# seeed2040_dev_board_11-13-22.net
KiCad netlist of a schematic drawn in EAGLE
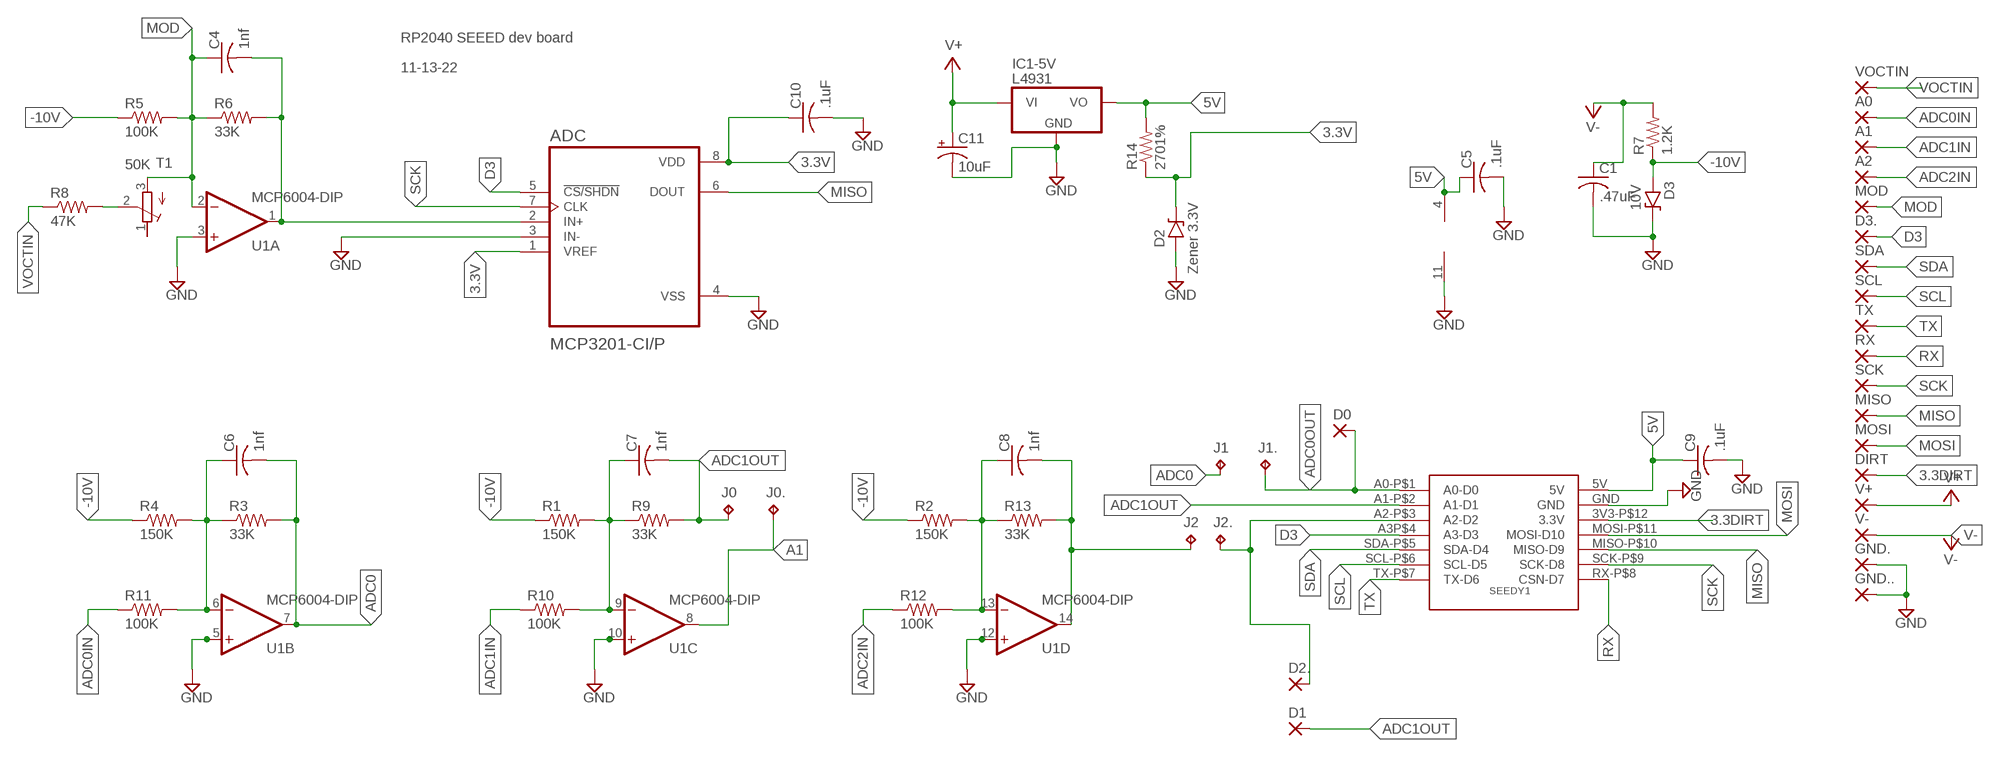
[diagram p0: schematic, sheet 1]

(export (version "E")
  (design (tool "Eeschema 10.0.6"))
  (components
    (comp (ref "A0")
      (value "WIREPAD1,6/0,9")
      (footprint "eagle-import:1,6_0,9")
      (libsource (lib "eagle-import") (part "WIREPAD1,6/0,9"))
    )
    (comp (ref "A1")
      (value "WIREPAD1,6/0,9")
      (footprint "eagle-import:1,6_0,9")
      (libsource (lib "eagle-import") (part "WIREPAD1,6/0,9"))
    )
    (comp (ref "A2")
      (value "WIREPAD1,6/0,9")
      (footprint "eagle-import:1,6_0,9")
      (libsource (lib "eagle-import") (part "WIREPAD1,6/0,9"))
    )
    (comp (ref "ADC")
      (value "MCP3201-CI/P")
      (footprint "eagle-import:DIP787W46P254L927H533Q8")
      (fields (field (name "MF") "Microchip Technology"))
      (libsource (lib "eagle-import") (part "MCP3201-CI/P"))
    )
    (comp (ref "C1")
      (value ".47uF")
      (footprint "eagle-import:C025-030X050")
      (libsource (lib "eagle-import") (part "rcl_334_C-US025-030X050"))
    )
    (comp (ref "C4")
      (value "1nf")
      (footprint "eagle-import:C025-025X050")
      (libsource (lib "eagle-import") (part "rcl_334_C-US025-025X050"))
    )
    (comp (ref "C5")
      (value ".1uF")
      (footprint "eagle-import:C025-025X050")
      (libsource (lib "eagle-import") (part "rcl_334_C-US025-025X050"))
    )
    (comp (ref "C6")
      (value "1nf")
      (footprint "eagle-import:C025-025X050")
      (libsource (lib "eagle-import") (part "rcl_334_C-US025-025X050"))
    )
    (comp (ref "C7")
      (value "1nf")
      (footprint "eagle-import:C025-025X050")
      (libsource (lib "eagle-import") (part "rcl_334_C-US025-025X050"))
    )
    (comp (ref "C8")
      (value "1nf")
      (footprint "eagle-import:C025-025X050")
      (libsource (lib "eagle-import") (part "rcl_334_C-US025-025X050"))
    )
    (comp (ref "C9")
      (value ".1uF")
      (footprint "eagle-import:C050-025X075")
      (libsource (lib "eagle-import") (part "C-US050-025X075"))
    )
    (comp (ref "C10")
      (value ".1uF")
      (footprint "eagle-import:C025-025X050")
      (libsource (lib "eagle-import") (part "rcl_334_C-US025-025X050"))
    )
    (comp (ref "C11")
      (value "10uF")
      (footprint "eagle-import:E2,5-7")
      (libsource (lib "eagle-import") (part "CPOL-USE2.5-7"))
    )
    (comp (ref "D0")
      (value "WIREPAD1,6/0,9")
      (footprint "eagle-import:1,6_0,9")
      (libsource (lib "eagle-import") (part "WIREPAD1,6/0,9"))
    )
    (comp (ref "D1")
      (value "WIREPAD1,6/0,9")
      (footprint "eagle-import:1,6_0,9")
      (libsource (lib "eagle-import") (part "WIREPAD1,6/0,9"))
    )
    (comp (ref "D2")
      (value "Zener 3.3V")
      (footprint "eagle-import:DO41-3")
      (libsource (lib "eagle-import") (part "ZENER.3"))
    )
    (comp (ref "D2.")
      (value "WIREPAD1,6/0,9")
      (footprint "eagle-import:1,6_0,9")
      (libsource (lib "eagle-import") (part "WIREPAD1,6/0,9"))
    )
    (comp (ref "D3")
      (value "10V")
      (footprint "eagle-import:DO41-3")
      (libsource (lib "eagle-import") (part "ZENER.3"))
    )
    (comp (ref "D3.")
      (value "WIREPAD1,6/0,9")
      (footprint "eagle-import:1,6_0,9")
      (libsource (lib "eagle-import") (part "WIREPAD1,6/0,9"))
    )
    (comp (ref "DIRT")
      (value "WIREPAD1,6/0,9")
      (footprint "eagle-import:1,6_0,9")
      (libsource (lib "eagle-import") (part "WIREPAD1,6/0,9"))
    )
    (comp (ref "GND.")
      (value "WIREPAD1,6/0,9")
      (footprint "eagle-import:1,6_0,9")
      (libsource (lib "eagle-import") (part "WIREPAD1,6/0,9"))
    )
    (comp (ref "GND..")
      (value "WIREPAD1,6/0,9")
      (footprint "eagle-import:1,6_0,9")
      (libsource (lib "eagle-import") (part "WIREPAD1,6/0,9"))
    )
    (comp (ref "IC1-5V")
      (value "L4931")
      (footprint "eagle-import:TO92-")
      (libsource (lib "eagle-import") (part "L4931"))
    )
    (comp (ref "J0")
      (value "TPPAD1-13")
      (footprint "eagle-import:P1-13")
      (libsource (lib "eagle-import") (part "TPPAD1-13"))
    )
    (comp (ref "J0.")
      (value "TPPAD1-13")
      (footprint "eagle-import:P1-13")
      (libsource (lib "eagle-import") (part "TPPAD1-13"))
    )
    (comp (ref "J1")
      (value "TPPAD1-13")
      (footprint "eagle-import:P1-13")
      (libsource (lib "eagle-import") (part "TPPAD1-13"))
    )
    (comp (ref "J1.")
      (value "TPPAD1-13")
      (footprint "eagle-import:P1-13")
      (libsource (lib "eagle-import") (part "TPPAD1-13"))
    )
    (comp (ref "J2")
      (value "TPPAD1-13")
      (footprint "eagle-import:P1-13")
      (libsource (lib "eagle-import") (part "TPPAD1-13"))
    )
    (comp (ref "J2.")
      (value "TPPAD1-13")
      (footprint "eagle-import:P1-13")
      (libsource (lib "eagle-import") (part "TPPAD1-13"))
    )
    (comp (ref "MISO")
      (value "WIREPAD1,6/0,9")
      (footprint "eagle-import:1,6_0,9")
      (libsource (lib "eagle-import") (part "WIREPAD1,6/0,9"))
    )
    (comp (ref "MOD")
      (value "WIREPAD1,6/0,9")
      (footprint "eagle-import:1,6_0,9")
      (libsource (lib "eagle-import") (part "WIREPAD1,6/0,9"))
    )
    (comp (ref "MOSI")
      (value "WIREPAD1,6/0,9")
      (footprint "eagle-import:1,6_0,9")
      (libsource (lib "eagle-import") (part "WIREPAD1,6/0,9"))
    )
    (comp (ref "R1")
      (value "150K")
      (footprint "eagle-import:0204_7")
      (libsource (lib "eagle-import") (part "R-US_0204/7"))
    )
    (comp (ref "R2")
      (value "150K")
      (footprint "eagle-import:0204_7")
      (libsource (lib "eagle-import") (part "R-US_0204/7"))
    )
    (comp (ref "R3")
      (value "33K")
      (footprint "eagle-import:0204_7")
      (libsource (lib "eagle-import") (part "R-US_0204/7"))
    )
    (comp (ref "R4")
      (value "150K")
      (footprint "eagle-import:0204_7")
      (libsource (lib "eagle-import") (part "R-US_0204/7"))
    )
    (comp (ref "R5")
      (value "100K")
      (footprint "eagle-import:0204_7")
      (libsource (lib "eagle-import") (part "R-US_0204/7"))
    )
    (comp (ref "R6")
      (value "33K")
      (footprint "eagle-import:0204_7")
      (libsource (lib "eagle-import") (part "R-US_0204/7"))
    )
    (comp (ref "R7")
      (value "1.2K")
      (footprint "eagle-import:0204_7")
      (libsource (lib "eagle-import") (part "R-US_0204/7"))
    )
    (comp (ref "R8")
      (value "47K")
      (footprint "eagle-import:0204_7")
      (libsource (lib "eagle-import") (part "R-US_0204/7"))
    )
    (comp (ref "R9")
      (value "33K")
      (footprint "eagle-import:0204_7")
      (libsource (lib "eagle-import") (part "R-US_0204/7"))
    )
    (comp (ref "R10")
      (value "100K")
      (footprint "eagle-import:0204_7")
      (libsource (lib "eagle-import") (part "R-US_0204/7"))
    )
    (comp (ref "R11")
      (value "100K")
      (footprint "eagle-import:0204_7")
      (libsource (lib "eagle-import") (part "R-US_0204/7"))
    )
    (comp (ref "R12")
      (value "100K")
      (footprint "eagle-import:0204_7")
      (libsource (lib "eagle-import") (part "R-US_0204/7"))
    )
    (comp (ref "R13")
      (value "33K")
      (footprint "eagle-import:0204_7")
      (libsource (lib "eagle-import") (part "R-US_0204/7"))
    )
    (comp (ref "R14")
      (value "2701%")
      (footprint "eagle-import:0204_7")
      (libsource (lib "eagle-import") (part "R-US_0204/7"))
    )
    (comp (ref "RX")
      (value "WIREPAD1,6/0,9")
      (footprint "eagle-import:1,6_0,9")
      (libsource (lib "eagle-import") (part "WIREPAD1,6/0,9"))
    )
    (comp (ref "SCK")
      (value "WIREPAD1,6/0,9")
      (footprint "eagle-import:1,6_0,9")
      (libsource (lib "eagle-import") (part "WIREPAD1,6/0,9"))
    )
    (comp (ref "SCL")
      (value "WIREPAD1,6/0,9")
      (footprint "eagle-import:1,6_0,9")
      (libsource (lib "eagle-import") (part "WIREPAD1,6/0,9"))
    )
    (comp (ref "SDA")
      (value "WIREPAD1,6/0,9")
      (footprint "eagle-import:1,6_0,9")
      (libsource (lib "eagle-import") (part "WIREPAD1,6/0,9"))
    )
    (comp (ref "SEEDY1")
      (value "SEEED_XIAO_RP2040")
      (footprint "eagle-import:14PIN700MIL")
      (libsource (lib "eagle-import") (part "SEEED_XIAO_RP2040"))
    )
    (comp (ref "T1")
      (value "50K")
      (footprint "eagle-import:RTRIMT93YA")
      (libsource (lib "eagle-import") (part "R-TRIMMT93YA"))
    )
    (comp (ref "TX")
      (value "WIREPAD1,6/0,9")
      (footprint "eagle-import:1,6_0,9")
      (libsource (lib "eagle-import") (part "WIREPAD1,6/0,9"))
    )
    (comp (ref "U1")
      (value "MCP6004-DIP")
      (footprint "eagle-import:DIL14")
      (libsource (lib "eagle-import") (part "MCP6004-DIP"))
    )
    (comp (ref "V+")
      (value "WIREPAD1,6/0,9")
      (footprint "eagle-import:1,6_0,9")
      (libsource (lib "eagle-import") (part "WIREPAD1,6/0,9"))
    )
    (comp (ref "V-")
      (value "WIREPAD1,6/0,9")
      (footprint "eagle-import:1,6_0,9")
      (libsource (lib "eagle-import") (part "WIREPAD1,6/0,9"))
    )
    (comp (ref "VOCTIN")
      (value "WIREPAD1,6/0,9")
      (footprint "eagle-import:1,6_0,9")
      (libsource (lib "eagle-import") (part "WIREPAD1,6/0,9"))
    )
  )
  (nets
    (net (code "1") (name "-10V") (class "Default")
      (node (ref "D3") (pin "A") (pinfunction "A_A") (pintype "passive"))
      (node (ref "R1") (pin "1") (pinfunction "1_1") (pintype "passive"))
      (node (ref "R2") (pin "1") (pinfunction "1_1") (pintype "passive"))
      (node (ref "R4") (pin "1") (pinfunction "1_1") (pintype "passive"))
      (node (ref "R5") (pin "1") (pinfunction "1_1") (pintype "passive"))
      (node (ref "R7") (pin "1") (pinfunction "1_1") (pintype "passive"))
    )
    (net (code "2") (name "3.3DIRT") (class "Default")
      (node (ref "DIRT") (pin "1") (pinfunction "P_1") (pintype "passive"))
      (node (ref "SEEDY1") (pin "3V3-P$12") (pinfunction "3.3V_3V3-P$12") (pintype "output"))
    )
    (net (code "3") (name "3.3V") (class "Default")
      (node (ref "ADC") (pin "1") (pinfunction "VREF_1") (pintype "input"))
      (node (ref "ADC") (pin "8") (pinfunction "VDD_8") (pintype "power_in"))
      (node (ref "C10") (pin "1") (pinfunction "1_1") (pintype "passive"))
      (node (ref "D2") (pin "C") (pinfunction "C_C") (pintype "passive"))
      (node (ref "R14") (pin "1") (pinfunction "1_1") (pintype "passive"))
    )
    (net (code "4") (name "5V") (class "Default")
      (node (ref "C5") (pin "1") (pinfunction "1_1") (pintype "passive"))
      (node (ref "C9") (pin "1") (pinfunction "1_1") (pintype "passive"))
      (node (ref "IC1-5V") (pin "3") (pinfunction "VO_3") (pintype "passive"))
      (node (ref "R14") (pin "2") (pinfunction "2_2") (pintype "passive"))
      (node (ref "SEEDY1") (pin "5V") (pinfunction "5V_5V") (pintype "power_in"))
      (node (ref "U1") (pin "4") (pinfunction "V+_4") (pintype "power_in"))
    )
    (net (code "5") (name "A1") (class "Default")
      (node (ref "J0.") (pin "TP") (pinfunction "TP_TP") (pintype "input"))
      (node (ref "U1") (pin "8") (pinfunction "OUT_8") (pintype "output"))
    )
    (net (code "6") (name "ADC0") (class "Default")
      (node (ref "C6") (pin "2") (pinfunction "2_2") (pintype "passive"))
      (node (ref "J1") (pin "TP") (pinfunction "TP_TP") (pintype "input"))
      (node (ref "R3") (pin "2") (pinfunction "2_2") (pintype "passive"))
      (node (ref "U1") (pin "7") (pinfunction "OUT_7") (pintype "output"))
    )
    (net (code "7") (name "ADC0IN") (class "Default")
      (node (ref "A0") (pin "1") (pinfunction "P_1") (pintype "passive"))
      (node (ref "R11") (pin "1") (pinfunction "1_1") (pintype "passive"))
    )
    (net (code "8") (name "ADC0OUT") (class "Default")
      (node (ref "D0") (pin "1") (pinfunction "P_1") (pintype "passive"))
      (node (ref "J1.") (pin "TP") (pinfunction "TP_TP") (pintype "input"))
      (node (ref "SEEDY1") (pin "A0-P$1") (pinfunction "A0-D0_A0-P$1") (pintype "bidirectional"))
    )
    (net (code "9") (name "ADC1IN") (class "Default")
      (node (ref "A1") (pin "1") (pinfunction "P_1") (pintype "passive"))
      (node (ref "R10") (pin "1") (pinfunction "1_1") (pintype "passive"))
    )
    (net (code "10") (name "ADC1OUT") (class "Default")
      (node (ref "C7") (pin "2") (pinfunction "2_2") (pintype "passive"))
      (node (ref "D1") (pin "1") (pinfunction "P_1") (pintype "passive"))
      (node (ref "J0") (pin "TP") (pinfunction "TP_TP") (pintype "input"))
      (node (ref "R9") (pin "2") (pinfunction "2_2") (pintype "passive"))
      (node (ref "SEEDY1") (pin "A1-P$2") (pinfunction "A1-D1_A1-P$2") (pintype "bidirectional"))
    )
    (net (code "11") (name "ADC2IN") (class "Default")
      (node (ref "A2") (pin "1") (pinfunction "P_1") (pintype "passive"))
      (node (ref "R12") (pin "1") (pinfunction "1_1") (pintype "passive"))
    )
    (net (code "12") (name "D3") (class "Default")
      (node (ref "ADC") (pin "5") (pinfunction "~{CS/SHDN}_5") (pintype "input"))
      (node (ref "D3.") (pin "1") (pinfunction "P_1") (pintype "passive"))
      (node (ref "SEEDY1") (pin "A3P$4") (pinfunction "A3-D3_A3P$4") (pintype "bidirectional"))
    )
    (net (code "13") (name "GND") (class "Default")
      (node (ref "ADC") (pin "3") (pinfunction "IN-_3") (pintype "input"))
      (node (ref "ADC") (pin "4") (pinfunction "VSS_4") (pintype "power_in"))
      (node (ref "C1") (pin "2") (pinfunction "2_2") (pintype "passive"))
      (node (ref "C10") (pin "2") (pinfunction "2_2") (pintype "passive"))
      (node (ref "C11") (pin "-") (pinfunction "-_-") (pintype "passive"))
      (node (ref "C5") (pin "2") (pinfunction "2_2") (pintype "passive"))
      (node (ref "C9") (pin "2") (pinfunction "2_2") (pintype "passive"))
      (node (ref "D2") (pin "A") (pinfunction "A_A") (pintype "passive"))
      (node (ref "D3") (pin "C") (pinfunction "C_C") (pintype "passive"))
      (node (ref "GND.") (pin "1") (pinfunction "P_1") (pintype "passive"))
      (node (ref "GND..") (pin "1") (pinfunction "P_1") (pintype "passive"))
      (node (ref "IC1-5V") (pin "2") (pinfunction "GND_2") (pintype "passive"))
      (node (ref "SEEDY1") (pin "GND") (pinfunction "GND_GND") (pintype "bidirectional"))
      (node (ref "U1") (pin "10") (pinfunction "+IN_10") (pintype "input"))
      (node (ref "U1") (pin "11") (pinfunction "V-_11") (pintype "power_in"))
      (node (ref "U1") (pin "12") (pinfunction "+IN_12") (pintype "input"))
      (node (ref "U1") (pin "3") (pinfunction "+IN_3") (pintype "input"))
      (node (ref "U1") (pin "5") (pinfunction "+IN_5") (pintype "input"))
    )
    (net (code "14") (name "MISO") (class "Default")
      (node (ref "ADC") (pin "6") (pinfunction "DOUT_6") (pintype "output"))
      (node (ref "MISO") (pin "1") (pinfunction "P_1") (pintype "passive"))
      (node (ref "SEEDY1") (pin "MISO-P$10") (pinfunction "MISO-D9_MISO-P$10") (pintype "bidirectional"))
    )
    (net (code "15") (name "MOD") (class "Default")
      (node (ref "C4") (pin "1") (pinfunction "1_1") (pintype "passive"))
      (node (ref "MOD") (pin "1") (pinfunction "P_1") (pintype "passive"))
      (node (ref "R5") (pin "2") (pinfunction "2_2") (pintype "passive"))
      (node (ref "R6") (pin "1") (pinfunction "1_1") (pintype "passive"))
      (node (ref "T1") (pin "3") (pinfunction "A_3") (pintype "passive"))
      (node (ref "U1") (pin "2") (pinfunction "-IN_2") (pintype "input"))
    )
    (net (code "16") (name "MOSI") (class "Default")
      (node (ref "MOSI") (pin "1") (pinfunction "P_1") (pintype "passive"))
      (node (ref "SEEDY1") (pin "MOSI-P$11") (pinfunction "MOSI-D10_MOSI-P$11") (pintype "bidirectional"))
    )
    (net (code "17") (name "Net-(ADC-IN+)") (class "Default")
      (node (ref "ADC") (pin "2") (pinfunction "IN+_2") (pintype "input"))
      (node (ref "C4") (pin "2") (pinfunction "2_2") (pintype "passive"))
      (node (ref "R6") (pin "2") (pinfunction "2_2") (pintype "passive"))
      (node (ref "U1") (pin "1") (pinfunction "OUT_1") (pintype "output"))
    )
    (net (code "18") (name "Net-(D2.-P)") (class "Default")
      (node (ref "D2.") (pin "1") (pinfunction "P_1") (pintype "passive"))
      (node (ref "J2.") (pin "TP") (pinfunction "TP_TP") (pintype "input"))
      (node (ref "SEEDY1") (pin "A2-P$3") (pinfunction "A2-D2_A2-P$3") (pintype "bidirectional"))
    )
    (net (code "19") (name "Net-(T1-S)") (class "Default")
      (node (ref "R8") (pin "2") (pinfunction "2_2") (pintype "passive"))
      (node (ref "T1") (pin "2") (pinfunction "S_2") (pintype "passive"))
    )
    (net (code "20") (name "Net-(U1B--IN)") (class "Default")
      (node (ref "C6") (pin "1") (pinfunction "1_1") (pintype "passive"))
      (node (ref "R11") (pin "2") (pinfunction "2_2") (pintype "passive"))
      (node (ref "R3") (pin "1") (pinfunction "1_1") (pintype "passive"))
      (node (ref "R4") (pin "2") (pinfunction "2_2") (pintype "passive"))
      (node (ref "U1") (pin "6") (pinfunction "-IN_6") (pintype "input"))
    )
    (net (code "21") (name "Net-(U1C--IN)") (class "Default")
      (node (ref "C7") (pin "1") (pinfunction "1_1") (pintype "passive"))
      (node (ref "R1") (pin "2") (pinfunction "2_2") (pintype "passive"))
      (node (ref "R10") (pin "2") (pinfunction "2_2") (pintype "passive"))
      (node (ref "R9") (pin "1") (pinfunction "1_1") (pintype "passive"))
      (node (ref "U1") (pin "9") (pinfunction "-IN_9") (pintype "input"))
    )
    (net (code "22") (name "Net-(U1D--IN)") (class "Default")
      (node (ref "C8") (pin "1") (pinfunction "1_1") (pintype "passive"))
      (node (ref "R12") (pin "2") (pinfunction "2_2") (pintype "passive"))
      (node (ref "R13") (pin "1") (pinfunction "1_1") (pintype "passive"))
      (node (ref "R2") (pin "2") (pinfunction "2_2") (pintype "passive"))
      (node (ref "U1") (pin "13") (pinfunction "-IN_13") (pintype "input"))
    )
    (net (code "23") (name "Net-(U1D-OUT)") (class "Default")
      (node (ref "C8") (pin "2") (pinfunction "2_2") (pintype "passive"))
      (node (ref "J2") (pin "TP") (pinfunction "TP_TP") (pintype "input"))
      (node (ref "R13") (pin "2") (pinfunction "2_2") (pintype "passive"))
      (node (ref "U1") (pin "14") (pinfunction "OUT_14") (pintype "output"))
    )
    (net (code "24") (name "RX") (class "Default")
      (node (ref "RX") (pin "1") (pinfunction "P_1") (pintype "passive"))
      (node (ref "SEEDY1") (pin "RX-P$8") (pinfunction "CSN-D7_RX-P$8") (pintype "bidirectional"))
    )
    (net (code "25") (name "SCK") (class "Default")
      (node (ref "ADC") (pin "7") (pinfunction "CLK_7") (pintype "input"))
      (node (ref "SCK") (pin "1") (pinfunction "P_1") (pintype "passive"))
      (node (ref "SEEDY1") (pin "SCK-P$9") (pinfunction "SCK-D8_SCK-P$9") (pintype "bidirectional"))
    )
    (net (code "26") (name "SCL") (class "Default")
      (node (ref "SCL") (pin "1") (pinfunction "P_1") (pintype "passive"))
      (node (ref "SEEDY1") (pin "SCL-P$6") (pinfunction "SCL-D5_SCL-P$6") (pintype "bidirectional"))
    )
    (net (code "27") (name "SDA") (class "Default")
      (node (ref "SDA") (pin "1") (pinfunction "P_1") (pintype "passive"))
      (node (ref "SEEDY1") (pin "SDA-P$5") (pinfunction "SDA-D4_SDA-P$5") (pintype "bidirectional"))
    )
    (net (code "28") (name "TX") (class "Default")
      (node (ref "SEEDY1") (pin "TX-P$7") (pinfunction "TX-D6_TX-P$7") (pintype "bidirectional"))
      (node (ref "TX") (pin "1") (pinfunction "P_1") (pintype "passive"))
    )
    (net (code "29") (name "V+") (class "Default")
      (node (ref "C11") (pin "+") (pinfunction "+_+") (pintype "passive"))
      (node (ref "IC1-5V") (pin "1") (pinfunction "VI_1") (pintype "input"))
      (node (ref "V+") (pin "1") (pinfunction "P_1") (pintype "passive"))
    )
    (net (code "30") (name "V-") (class "Default")
      (node (ref "C1") (pin "1") (pinfunction "1_1") (pintype "passive"))
      (node (ref "R7") (pin "2") (pinfunction "2_2") (pintype "passive"))
      (node (ref "V-") (pin "1") (pinfunction "P_1") (pintype "passive"))
    )
    (net (code "31") (name "VOCTIN") (class "Default")
      (node (ref "R8") (pin "1") (pinfunction "1_1") (pintype "passive"))
      (node (ref "VOCTIN") (pin "1") (pinfunction "P_1") (pintype "passive"))
    )
    (net (code "32") (name "unconnected-(T1-E-Pad1)") (class "Default")
      (node (ref "T1") (pin "1") (pinfunction "E_1") (pintype "passive"))
    )
  )
)
